# DS3_CONTROLLER_L.net
KiCad netlist of a schematic drawn in EasyEDA Pro
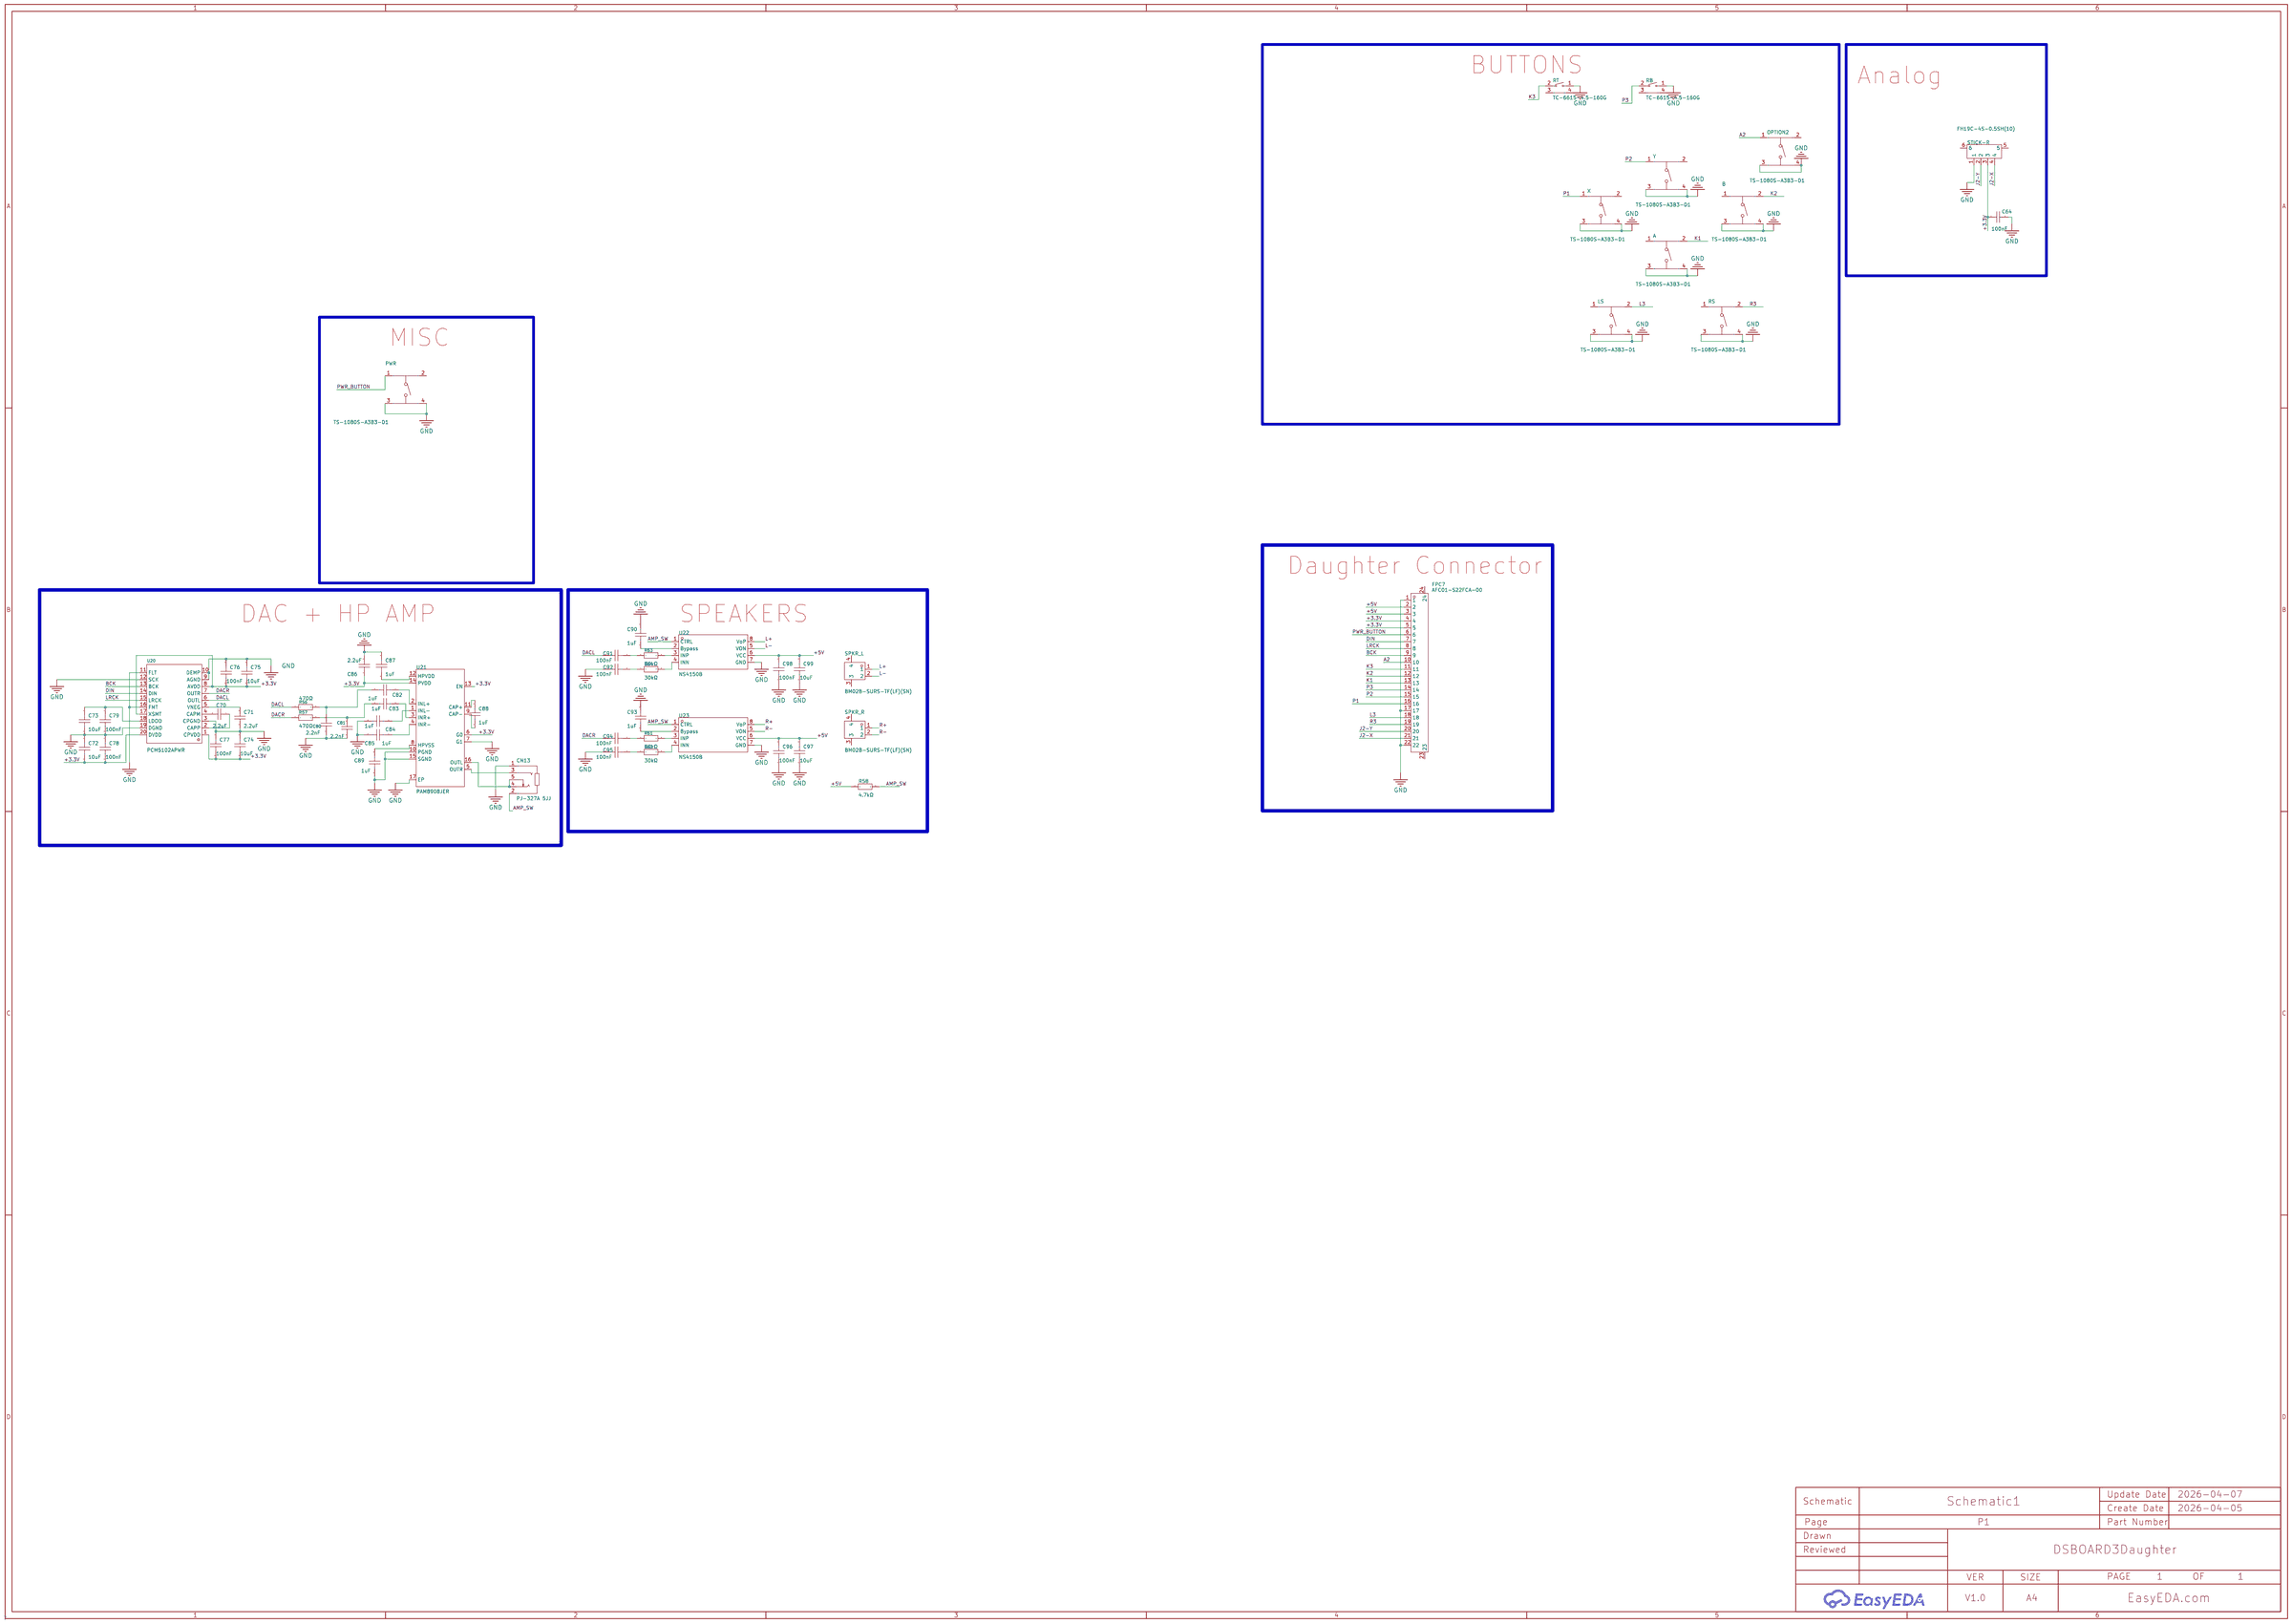
[diagram p0: schematic sheet]

(export (version "E")
  (design (tool "Eeschema 10.0.6"))
  (components
    (comp (ref "A")
      (value "TS-1080S-A3B3-D1")
      (footprint "easyedapro:KEY-SMD_4P-L6.0-W6.0-P4.50-LS9.5-BL")
      (fields (field (name "Manufacturer") "Yuandi(元迪)"))
      (libsource (lib "easyedapro") (part "K2-1102SP-C4SC-04"))
    )
    (comp (ref "B")
      (value "TS-1080S-A3B3-D1")
      (footprint "easyedapro:KEY-SMD_4P-L6.0-W6.0-P4.50-LS9.5-BL")
      (fields (field (name "Manufacturer") "Yuandi(元迪)"))
      (libsource (lib "easyedapro") (part "K2-1102SP-C4SC-04"))
    )
    (comp (ref "C64")
      (value "100nF")
      (footprint "easyedapro:C0402_NEW")
      (fields
        (field (name "Manufacturer Part") "CL05B104KO5NNNC")
        (field (name "Manufacturer") "SAMSUNG(三星)")
      )
      (libsource (lib "easyedapro") (part "100nF"))
    )
    (comp (ref "C70")
      (value "2.2uF")
      (footprint "easyedapro:C0603")
      (fields
        (field (name "Manufacturer Part") "CL10A225KO8NNNC")
        (field (name "Manufacturer") "SAMSUNG(三星)")
      )
      (libsource (lib "easyedapro") (part "CL10A225KO8NNNC"))
    )
    (comp (ref "C71")
      (value "2.2uF")
      (footprint "easyedapro:C0603")
      (fields
        (field (name "Manufacturer Part") "CL10A225KO8NNNC")
        (field (name "Manufacturer") "SAMSUNG(三星)")
      )
      (libsource (lib "easyedapro") (part "CL10A225KO8NNNC"))
    )
    (comp (ref "C72")
      (value "10uF")
      (footprint "easyedapro:C0805")
      (fields
        (field (name "Manufacturer Part") "GRM21BR61H106KE43L")
        (field (name "Manufacturer") "muRata(村田)")
      )
      (libsource (lib "easyedapro") (part "GRM21BR61H106KE43L"))
    )
    (comp (ref "C73")
      (value "10uF")
      (footprint "easyedapro:C0805")
      (fields
        (field (name "Manufacturer Part") "GRM21BR61H106KE43L")
        (field (name "Manufacturer") "muRata(村田)")
      )
      (libsource (lib "easyedapro") (part "GRM21BR61H106KE43L"))
    )
    (comp (ref "C74")
      (value "10uF")
      (footprint "easyedapro:C0805")
      (fields
        (field (name "Manufacturer Part") "GRM21BR61H106KE43L")
        (field (name "Manufacturer") "muRata(村田)")
      )
      (libsource (lib "easyedapro") (part "GRM21BR61H106KE43L"))
    )
    (comp (ref "C75")
      (value "10uF")
      (footprint "easyedapro:C0805")
      (fields
        (field (name "Manufacturer Part") "GRM21BR61H106KE43L")
        (field (name "Manufacturer") "muRata(村田)")
      )
      (libsource (lib "easyedapro") (part "GRM21BR61H106KE43L"))
    )
    (comp (ref "C76")
      (value "100nF")
      (footprint "easyedapro:C0603")
      (description "Capacitance:100nF Tolerance:±10% Tolerance:±10% Voltage Rating:50V Temperature Coefficient:X7R")
      (fields
        (field (name "Manufacturer Part") "CC0603KRX7R9BB104")
        (field (name "Manufacturer") "YAGEO(国巨)")
      )
      (libsource (lib "easyedapro") (part "CC0603KRX7R9BB104"))
    )
    (comp (ref "C77")
      (value "100nF")
      (footprint "easyedapro:C0603")
      (description "Capacitance:100nF Tolerance:±10% Tolerance:±10% Voltage Rating:50V Temperature Coefficient:X7R")
      (fields
        (field (name "Manufacturer Part") "CC0603KRX7R9BB104")
        (field (name "Manufacturer") "YAGEO(国巨)")
      )
      (libsource (lib "easyedapro") (part "CC0603KRX7R9BB104"))
    )
    (comp (ref "C78")
      (value "100nF")
      (footprint "easyedapro:C0603")
      (description "Capacitance:100nF Tolerance:±10% Tolerance:±10% Voltage Rating:50V Temperature Coefficient:X7R")
      (fields
        (field (name "Manufacturer Part") "CC0603KRX7R9BB104")
        (field (name "Manufacturer") "YAGEO(国巨)")
      )
      (libsource (lib "easyedapro") (part "CC0603KRX7R9BB104"))
    )
    (comp (ref "C79")
      (value "100nF")
      (footprint "easyedapro:C0603")
      (description "Capacitance:100nF Tolerance:±10% Tolerance:±10% Voltage Rating:50V Temperature Coefficient:X7R")
      (fields
        (field (name "Manufacturer Part") "CC0603KRX7R9BB104")
        (field (name "Manufacturer") "YAGEO(国巨)")
      )
      (libsource (lib "easyedapro") (part "CC0603KRX7R9BB104"))
    )
    (comp (ref "C80")
      (value "2.2nF")
      (footprint "easyedapro:C0805")
      (fields
        (field (name "Manufacturer Part") "CL21C222JBFNNNE")
        (field (name "Manufacturer") "SAMSUNG(三星)")
      )
      (libsource (lib "easyedapro") (part "CL21C222JBFNNNE"))
    )
    (comp (ref "C81")
      (value "2.2nF")
      (footprint "easyedapro:C0805")
      (fields
        (field (name "Manufacturer Part") "CL21C222JBFNNNE")
        (field (name "Manufacturer") "SAMSUNG(三星)")
      )
      (libsource (lib "easyedapro") (part "CL21C222JBFNNNE"))
    )
    (comp (ref "C82")
      (value "1uF")
      (footprint "easyedapro:C0603")
      (fields
        (field (name "Manufacturer Part") "CL10A105KB8NNNC")
        (field (name "Manufacturer") "SAMSUNG(三星)")
      )
      (libsource (lib "easyedapro") (part "CL10A105KB8NNNC"))
    )
    (comp (ref "C83")
      (value "1uF")
      (footprint "easyedapro:C0603")
      (fields
        (field (name "Manufacturer Part") "CL10A105KB8NNNC")
        (field (name "Manufacturer") "SAMSUNG(三星)")
      )
      (libsource (lib "easyedapro") (part "CL10A105KB8NNNC"))
    )
    (comp (ref "C84")
      (value "1uF")
      (footprint "easyedapro:C0603")
      (fields
        (field (name "Manufacturer Part") "CL10A105KB8NNNC")
        (field (name "Manufacturer") "SAMSUNG(三星)")
      )
      (libsource (lib "easyedapro") (part "CL10A105KB8NNNC"))
    )
    (comp (ref "C85")
      (value "1uF")
      (footprint "easyedapro:C0603")
      (fields
        (field (name "Manufacturer Part") "CL10A105KB8NNNC")
        (field (name "Manufacturer") "SAMSUNG(三星)")
      )
      (libsource (lib "easyedapro") (part "CL10A105KB8NNNC"))
    )
    (comp (ref "C86")
      (value "2.2uF")
      (footprint "easyedapro:C0603")
      (fields
        (field (name "Manufacturer Part") "CL10A225KO8NNNC")
        (field (name "Manufacturer") "SAMSUNG(三星)")
      )
      (libsource (lib "easyedapro") (part "CL10A225KO8NNNC"))
    )
    (comp (ref "C87")
      (value "1uF")
      (footprint "easyedapro:C0603")
      (fields
        (field (name "Manufacturer Part") "CL10A105KB8NNNC")
        (field (name "Manufacturer") "SAMSUNG(三星)")
      )
      (libsource (lib "easyedapro") (part "CL10A105KB8NNNC"))
    )
    (comp (ref "C88")
      (value "1uF")
      (footprint "easyedapro:C0603")
      (fields
        (field (name "Manufacturer Part") "CL10A105KB8NNNC")
        (field (name "Manufacturer") "SAMSUNG(三星)")
      )
      (libsource (lib "easyedapro") (part "CL10A105KB8NNNC"))
    )
    (comp (ref "C89")
      (value "1uF")
      (footprint "easyedapro:C0603")
      (fields
        (field (name "Manufacturer Part") "CL10A105KB8NNNC")
        (field (name "Manufacturer") "SAMSUNG(三星)")
      )
      (libsource (lib "easyedapro") (part "CL10A105KB8NNNC"))
    )
    (comp (ref "C90")
      (value "1uF")
      (footprint "easyedapro:C0603")
      (fields
        (field (name "Manufacturer Part") "CL10A105KB8NNNC")
        (field (name "Manufacturer") "SAMSUNG(三星)")
      )
      (libsource (lib "easyedapro") (part "CL10A105KB8NNNC"))
    )
    (comp (ref "C91")
      (value "100nF")
      (footprint "easyedapro:C0402")
      (fields
        (field (name "Manufacturer Part") "CL05B104KB54PNC")
        (field (name "Manufacturer") "SAMSUNG(三星)")
      )
      (libsource (lib "easyedapro") (part "CL05B104KB54PNC"))
    )
    (comp (ref "C92")
      (value "100nF")
      (footprint "easyedapro:C0402")
      (fields
        (field (name "Manufacturer Part") "CL05B104KB54PNC")
        (field (name "Manufacturer") "SAMSUNG(三星)")
      )
      (libsource (lib "easyedapro") (part "CL05B104KB54PNC"))
    )
    (comp (ref "C93")
      (value "1uF")
      (footprint "easyedapro:C0603")
      (fields
        (field (name "Manufacturer Part") "CL10A105KB8NNNC")
        (field (name "Manufacturer") "SAMSUNG(三星)")
      )
      (libsource (lib "easyedapro") (part "CL10A105KB8NNNC"))
    )
    (comp (ref "C94")
      (value "100nF")
      (footprint "easyedapro:C0402")
      (fields
        (field (name "Manufacturer Part") "CL05B104KB54PNC")
        (field (name "Manufacturer") "SAMSUNG(三星)")
      )
      (libsource (lib "easyedapro") (part "CL05B104KB54PNC"))
    )
    (comp (ref "C95")
      (value "100nF")
      (footprint "easyedapro:C0402")
      (fields
        (field (name "Manufacturer Part") "CL05B104KB54PNC")
        (field (name "Manufacturer") "SAMSUNG(三星)")
      )
      (libsource (lib "easyedapro") (part "CL05B104KB54PNC"))
    )
    (comp (ref "C96")
      (value "100nF")
      (footprint "easyedapro:C0402")
      (fields
        (field (name "Manufacturer Part") "CL05B104KB54PNC")
        (field (name "Manufacturer") "SAMSUNG(三星)")
      )
      (libsource (lib "easyedapro") (part "CL05B104KB54PNC"))
    )
    (comp (ref "C97")
      (value "10uF")
      (footprint "easyedapro:C0805")
      (fields
        (field (name "Manufacturer Part") "CL21A106KAYNNNE")
        (field (name "Manufacturer") "SAMSUNG(三星)")
      )
      (libsource (lib "easyedapro") (part "CL21A106KAYNNNE"))
    )
    (comp (ref "C98")
      (value "100nF")
      (footprint "easyedapro:C0402")
      (fields
        (field (name "Manufacturer Part") "CL05B104KB54PNC")
        (field (name "Manufacturer") "SAMSUNG(三星)")
      )
      (libsource (lib "easyedapro") (part "CL05B104KB54PNC"))
    )
    (comp (ref "C99")
      (value "10uF")
      (footprint "easyedapro:C0805")
      (fields
        (field (name "Manufacturer Part") "CL21A106KAYNNNE")
        (field (name "Manufacturer") "SAMSUNG(三星)")
      )
      (libsource (lib "easyedapro") (part "CL21A106KAYNNNE"))
    )
    (comp (ref "CN13")
      (value "PJ-327A 5JJ")
      (footprint "easyedapro:AUDIO-SMD_PJ-327A5JJ")
      (fields (field (name "Manufacturer") "SHOU HAN(首韩)"))
      (libsource (lib "easyedapro") (part "PJ-327A 5JJ"))
    )
    (comp (ref "FPC7")
      (value "AFC01-S22FCA-00")
      (footprint "easyedapro:FPC-SMD_P0.5-22P_FGS-XJ-H2.0")
      (fields (field (name "Manufacturer") "JS(钜硕电子)"))
      (libsource (lib "easyedapro") (part "fh12-22s-0.5sh(55)"))
    )
    (comp (ref "LS")
      (value "TS-1080S-A3B3-D1")
      (footprint "easyedapro:KEY-SMD_4P-L6.0-W6.0-P4.50-LS9.5-BL")
      (fields (field (name "Manufacturer") "Yuandi(元迪)"))
      (libsource (lib "easyedapro") (part "K2-1102SP-C4SC-04"))
    )
    (comp (ref "OPTION2")
      (value "TS-1080S-A3B3-D1")
      (footprint "easyedapro:KEY-SMD_4P-L6.0-W6.0-P4.50-LS9.5-BL")
      (fields (field (name "Manufacturer") "Yuandi(元迪)"))
      (libsource (lib "easyedapro") (part "K2-1102SP-C4SC-04"))
    )
    (comp (ref "PWR")
      (value "TS-1080S-A3B3-D1")
      (footprint "easyedapro:KEY-SMD_4P-L6.0-W6.0-P4.50-LS9.5-BL")
      (fields (field (name "Manufacturer") "Yuandi(元迪)"))
      (libsource (lib "easyedapro") (part "K2-1102SP-C4SC-04"))
    )
    (comp (ref "R56")
      (value "470Ω")
      (footprint "easyedapro:R0805")
      (fields
        (field (name "Manufacturer Part") "0805W8F4700T5E")
        (field (name "Manufacturer") "UNI-ROYAL(厚声)")
      )
      (libsource (lib "easyedapro") (part "0805W8F4700T5E"))
    )
    (comp (ref "R57")
      (value "470Ω")
      (footprint "easyedapro:R0805")
      (fields
        (field (name "Manufacturer Part") "0805W8F4700T5E")
        (field (name "Manufacturer") "UNI-ROYAL(厚声)")
      )
      (libsource (lib "easyedapro") (part "0805W8F4700T5E"))
    )
    (comp (ref "R58")
      (value "4.7kΩ")
      (footprint "easyedapro:R0603")
      (fields
        (field (name "Manufacturer Part") "0603WAF4701T5E")
        (field (name "Manufacturer") "UNI-ROYAL(厚声)")
      )
      (libsource (lib "easyedapro") (part "0603WAF4701T5E"))
    )
    (comp (ref "R61")
      (value "30kΩ")
      (footprint "easyedapro:R0603")
      (fields
        (field (name "Manufacturer Part") "0603WAF3002T5E")
        (field (name "Manufacturer") "UNI-ROYAL(厚声)")
      )
      (libsource (lib "easyedapro") (part "0603WAF3002T5E"))
    )
    (comp (ref "R62")
      (value "30kΩ")
      (footprint "easyedapro:R0603")
      (fields
        (field (name "Manufacturer Part") "0603WAF3002T5E")
        (field (name "Manufacturer") "UNI-ROYAL(厚声)")
      )
      (libsource (lib "easyedapro") (part "0603WAF3002T5E"))
    )
    (comp (ref "R63")
      (value "30kΩ")
      (footprint "easyedapro:R0603")
      (fields
        (field (name "Manufacturer Part") "0603WAF3002T5E")
        (field (name "Manufacturer") "UNI-ROYAL(厚声)")
      )
      (libsource (lib "easyedapro") (part "0603WAF3002T5E"))
    )
    (comp (ref "R64")
      (value "30kΩ")
      (footprint "easyedapro:R0603")
      (fields
        (field (name "Manufacturer Part") "0603WAF3002T5E")
        (field (name "Manufacturer") "UNI-ROYAL(厚声)")
      )
      (libsource (lib "easyedapro") (part "0603WAF3002T5E"))
    )
    (comp (ref "RB")
      (value "TC-6615-4.5-160G")
      (footprint "easyedapro:KEY-TH_TC-6615-4.5-160G")
      (fields (field (name "Manufacturer") "HCTL(华灿天禄)"))
      (libsource (lib "easyedapro") (part "TC-6615-4.5-160G"))
    )
    (comp (ref "RS")
      (value "TS-1080S-A3B3-D1")
      (footprint "easyedapro:KEY-SMD_4P-L6.0-W6.0-P4.50-LS9.5-BL")
      (fields (field (name "Manufacturer") "Yuandi(元迪)"))
      (libsource (lib "easyedapro") (part "K2-1102SP-C4SC-04"))
    )
    (comp (ref "RT")
      (value "TC-6615-4.5-160G")
      (footprint "easyedapro:KEY-TH_TC-6615-4.5-160G")
      (fields (field (name "Manufacturer") "HCTL(华灿天禄)"))
      (libsource (lib "easyedapro") (part "TC-6615-4.5-160G"))
    )
    (comp (ref "SPKR_L")
      (value "BM02B-SURS-TF(LF)(SN)")
      (footprint "easyedapro:CONN-SMD_2P-P0.80_BM02B-SURS-TF-LF-SN")
      (fields (field (name "Manufacturer") "JST"))
      (libsource (lib "easyedapro") (part "BM02B-SURS-TF(LF)(SN)"))
    )
    (comp (ref "SPKR_R")
      (value "BM02B-SURS-TF(LF)(SN)")
      (footprint "easyedapro:CONN-SMD_2P-P0.80_BM02B-SURS-TF-LF-SN")
      (fields (field (name "Manufacturer") "JST"))
      (libsource (lib "easyedapro") (part "BM02B-SURS-TF(LF)(SN)"))
    )
    (comp (ref "STICK-R")
      (value "FH19C-4S-0.5SH(10)")
      (fields (field (name "Manufacturer") "HRS(广濑)"))
      (libsource (lib "easyedapro") (part "fh34srj-4s-0.5sh(50)"))
    )
    (comp (ref "U20")
      (value "PCM5102APWR")
      (footprint "easyedapro:TSSOP-20_L6.5-W4.4-P0.65-LS6.4-BL")
      (fields (field (name "Manufacturer") "TI(德州仪器)"))
      (libsource (lib "easyedapro") (part "PCM5102APWR"))
    )
    (comp (ref "U21")
      (value "PAM8908JER")
      (footprint "easyedapro:QFN-16_L3.0-W3.0-P0.50-BL-EP1.7")
      (fields (field (name "Manufacturer") "DIODES(美台)"))
      (libsource (lib "easyedapro") (part "PAM8908JER"))
    )
    (comp (ref "U22")
      (value "NS4150B")
      (footprint "easyedapro:MSOP-8_L3.0-W3.0-P0.65-LS5.0-BL")
      (description "Class:Class D Output Power:3Wx1@4Ω Voltage - Supply:3V~5.25V Voltage - Supply:3V~5.25V")
      (fields (field (name "Manufacturer") "Nsiway(纳芯威)"))
      (libsource (lib "easyedapro") (part "NS4150"))
    )
    (comp (ref "U23")
      (value "NS4150B")
      (footprint "easyedapro:MSOP-8_L3.0-W3.0-P0.65-LS5.0-BL")
      (description "Class:Class D Output Power:3Wx1@4Ω Voltage - Supply:3V~5.25V Voltage - Supply:3V~5.25V")
      (fields (field (name "Manufacturer") "Nsiway(纳芯威)"))
      (libsource (lib "easyedapro") (part "NS4150"))
    )
    (comp (ref "X")
      (value "TS-1080S-A3B3-D1")
      (footprint "easyedapro:KEY-SMD_4P-L6.0-W6.0-P4.50-LS9.5-BL")
      (fields (field (name "Manufacturer") "Yuandi(元迪)"))
      (libsource (lib "easyedapro") (part "K2-1102SP-C4SC-04"))
    )
    (comp (ref "Y")
      (value "TS-1080S-A3B3-D1")
      (footprint "easyedapro:KEY-SMD_4P-L6.0-W6.0-P4.50-LS9.5-BL")
      (fields (field (name "Manufacturer") "Yuandi(元迪)"))
      (libsource (lib "easyedapro") (part "K2-1102SP-C4SC-04"))
    )
  )
  (nets
    (net (code "1") (name "/+3.3V") (class "Default")
      (node (ref "C64") (pin "1") (pinfunction "1_1") (pintype "input"))
      (node (ref "C72") (pin "2") (pinfunction "2_2") (pintype "unspecified"))
      (node (ref "C74") (pin "2") (pinfunction "2_2") (pintype "unspecified"))
      (node (ref "C75") (pin "2") (pinfunction "2_2") (pintype "unspecified"))
      (node (ref "C76") (pin "2") (pinfunction "2_2") (pintype "unspecified"))
      (node (ref "C77") (pin "2") (pinfunction "2_2") (pintype "unspecified"))
      (node (ref "C78") (pin "2") (pinfunction "2_2") (pintype "unspecified"))
      (node (ref "C86") (pin "1") (pinfunction "1_1") (pintype "input"))
      (node (ref "FPC7") (pin "4") (pinfunction "4_4") (pintype "input"))
      (node (ref "FPC7") (pin "5") (pinfunction "5_5") (pintype "input"))
      (node (ref "STICK-R") (pin "3") (pinfunction "3_3") (pintype "unspecified"))
      (node (ref "U20") (pin "1") (pinfunction "CPVDD_1") (pintype "input"))
      (node (ref "U20") (pin "17") (pinfunction "XSMT_17") (pintype "input"))
      (node (ref "U20") (pin "20") (pinfunction "DVDD_20") (pintype "input"))
      (node (ref "U20") (pin "8") (pinfunction "AVDD_8") (pintype "input"))
      (node (ref "U21") (pin "13") (pinfunction "EN_13") (pintype "unspecified"))
      (node (ref "U21") (pin "14") (pinfunction "PVDD_14") (pintype "unspecified"))
      (node (ref "U21") (pin "6") (pinfunction "G0_6") (pintype "unspecified"))
    )
    (net (code "2") (name "/+5V") (class "Default")
      (node (ref "C96") (pin "2") (pinfunction "2_2") (pintype "input"))
      (node (ref "C97") (pin "2") (pinfunction "2_2") (pintype "unspecified"))
      (node (ref "C98") (pin "2") (pinfunction "2_2") (pintype "input"))
      (node (ref "C99") (pin "2") (pinfunction "2_2") (pintype "unspecified"))
      (node (ref "FPC7") (pin "2") (pinfunction "2_2") (pintype "input"))
      (node (ref "FPC7") (pin "3") (pinfunction "3_3") (pintype "input"))
      (node (ref "R58") (pin "1") (pinfunction "1_1") (pintype "input"))
      (node (ref "U22") (pin "6") (pinfunction "VCC_6") (pintype "unspecified"))
      (node (ref "U23") (pin "6") (pinfunction "VCC_6") (pintype "unspecified"))
    )
    (net (code "3") (name "/A2") (class "Default")
      (node (ref "FPC7") (pin "10") (pinfunction "10_10") (pintype "input"))
      (node (ref "OPTION2") (pin "1") (pinfunction "1_1") (pintype "unspecified"))
    )
    (net (code "4") (name "/AMP_SW") (class "Default")
      (node (ref "CN13") (pin "2") (pinfunction "2_2") (pintype "unspecified"))
      (node (ref "R58") (pin "2") (pinfunction "2_2") (pintype "input"))
      (node (ref "U22") (pin "1") (pinfunction "CTRL_1") (pintype "unspecified"))
      (node (ref "U23") (pin "1") (pinfunction "CTRL_1") (pintype "unspecified"))
    )
    (net (code "5") (name "/BCK") (class "Default")
      (node (ref "FPC7") (pin "9") (pinfunction "9_9") (pintype "input"))
      (node (ref "U20") (pin "13") (pinfunction "BCK_13") (pintype "input"))
    )
    (net (code "6") (name "/DACL") (class "Default")
      (node (ref "C91") (pin "1") (pinfunction "1_1") (pintype "input"))
      (node (ref "R56") (pin "1") (pinfunction "1_1") (pintype "input"))
      (node (ref "U20") (pin "6") (pinfunction "OUTL_6") (pintype "input"))
    )
    (net (code "7") (name "/DACR") (class "Default")
      (node (ref "C94") (pin "1") (pinfunction "1_1") (pintype "input"))
      (node (ref "R57") (pin "1") (pinfunction "1_1") (pintype "input"))
      (node (ref "U20") (pin "7") (pinfunction "OUTR_7") (pintype "input"))
    )
    (net (code "8") (name "/DIN") (class "Default")
      (node (ref "FPC7") (pin "7") (pinfunction "7_7") (pintype "input"))
      (node (ref "U20") (pin "14") (pinfunction "DIN_14") (pintype "input"))
    )
    (net (code "9") (name "/J2-X") (class "Default")
      (node (ref "FPC7") (pin "21") (pinfunction "21_21") (pintype "input"))
      (node (ref "STICK-R") (pin "4") (pinfunction "4_4") (pintype "unspecified"))
    )
    (net (code "10") (name "/J2-Y") (class "Default")
      (node (ref "FPC7") (pin "20") (pinfunction "20_20") (pintype "input"))
      (node (ref "STICK-R") (pin "2") (pinfunction "2_2") (pintype "unspecified"))
    )
    (net (code "11") (name "/K1") (class "Default")
      (node (ref "A") (pin "2") (pinfunction "2_2") (pintype "unspecified"))
      (node (ref "FPC7") (pin "13") (pinfunction "13_13") (pintype "input"))
    )
    (net (code "12") (name "/K2") (class "Default")
      (node (ref "B") (pin "2") (pinfunction "2_2") (pintype "unspecified"))
      (node (ref "FPC7") (pin "12") (pinfunction "12_12") (pintype "input"))
    )
    (net (code "13") (name "/K3") (class "Default")
      (node (ref "FPC7") (pin "11") (pinfunction "11_11") (pintype "input"))
      (node (ref "RT") (pin "2") (pinfunction "2_2") (pintype "unspecified"))
    )
    (net (code "14") (name "/L+") (class "Default")
      (node (ref "SPKR_L") (pin "1") (pinfunction "1_1") (pintype "unspecified"))
      (node (ref "U22") (pin "8") (pinfunction "VoP_8") (pintype "unspecified"))
    )
    (net (code "15") (name "/L-") (class "Default")
      (node (ref "SPKR_L") (pin "2") (pinfunction "2_2") (pintype "unspecified"))
      (node (ref "U22") (pin "5") (pinfunction "VON_5") (pintype "unspecified"))
    )
    (net (code "16") (name "/L3") (class "Default")
      (node (ref "FPC7") (pin "18") (pinfunction "18_18") (pintype "input"))
      (node (ref "LS") (pin "2") (pinfunction "2_2") (pintype "unspecified"))
    )
    (net (code "17") (name "/LRCK") (class "Default")
      (node (ref "FPC7") (pin "8") (pinfunction "8_8") (pintype "input"))
      (node (ref "U20") (pin "15") (pinfunction "LRCK_15") (pintype "input"))
    )
    (net (code "18") (name "/P1") (class "Default")
      (node (ref "FPC7") (pin "16") (pinfunction "16_16") (pintype "input"))
      (node (ref "X") (pin "1") (pinfunction "1_1") (pintype "unspecified"))
    )
    (net (code "19") (name "/P2") (class "Default")
      (node (ref "FPC7") (pin "15") (pinfunction "15_15") (pintype "input"))
      (node (ref "Y") (pin "1") (pinfunction "1_1") (pintype "unspecified"))
    )
    (net (code "20") (name "/P3") (class "Default")
      (node (ref "FPC7") (pin "14") (pinfunction "14_14") (pintype "input"))
      (node (ref "RB") (pin "2") (pinfunction "2_2") (pintype "unspecified"))
    )
    (net (code "21") (name "/PWR_BUTTON") (class "Default")
      (node (ref "FPC7") (pin "6") (pinfunction "6_6") (pintype "input"))
      (node (ref "PWR") (pin "1") (pinfunction "1_1") (pintype "unspecified"))
    )
    (net (code "22") (name "/R+") (class "Default")
      (node (ref "SPKR_R") (pin "1") (pinfunction "1_1") (pintype "unspecified"))
      (node (ref "U23") (pin "8") (pinfunction "VoP_8") (pintype "unspecified"))
    )
    (net (code "23") (name "/R-") (class "Default")
      (node (ref "SPKR_R") (pin "2") (pinfunction "2_2") (pintype "unspecified"))
      (node (ref "U23") (pin "5") (pinfunction "VON_5") (pintype "unspecified"))
    )
    (net (code "24") (name "/R3") (class "Default")
      (node (ref "FPC7") (pin "19") (pinfunction "19_19") (pintype "input"))
      (node (ref "RS") (pin "2") (pinfunction "2_2") (pintype "unspecified"))
    )
    (net (code "25") (name "GND") (class "Default")
      (node (ref "A") (pin "3") (pinfunction "3_3") (pintype "unspecified"))
      (node (ref "A") (pin "4") (pinfunction "4_4") (pintype "unspecified"))
      (node (ref "B") (pin "3") (pinfunction "3_3") (pintype "unspecified"))
      (node (ref "B") (pin "4") (pinfunction "4_4") (pintype "unspecified"))
      (node (ref "C64") (pin "2") (pinfunction "2_2") (pintype "input"))
      (node (ref "C71") (pin "1") (pinfunction "1_1") (pintype "input"))
      (node (ref "C72") (pin "1") (pinfunction "1_1") (pintype "unspecified"))
      (node (ref "C73") (pin "2") (pinfunction "2_2") (pintype "unspecified"))
      (node (ref "C74") (pin "1") (pinfunction "1_1") (pintype "unspecified"))
      (node (ref "C75") (pin "1") (pinfunction "1_1") (pintype "unspecified"))
      (node (ref "C76") (pin "1") (pinfunction "1_1") (pintype "unspecified"))
      (node (ref "C77") (pin "1") (pinfunction "1_1") (pintype "unspecified"))
      (node (ref "C78") (pin "1") (pinfunction "1_1") (pintype "unspecified"))
      (node (ref "C79") (pin "2") (pinfunction "2_2") (pintype "unspecified"))
      (node (ref "C80") (pin "2") (pinfunction "2_2") (pintype "input"))
      (node (ref "C81") (pin "2") (pinfunction "2_2") (pintype "input"))
      (node (ref "C84") (pin "2") (pinfunction "2_2") (pintype "unspecified"))
      (node (ref "C85") (pin "2") (pinfunction "2_2") (pintype "unspecified"))
      (node (ref "C86") (pin "2") (pinfunction "2_2") (pintype "input"))
      (node (ref "C87") (pin "2") (pinfunction "2_2") (pintype "unspecified"))
      (node (ref "C89") (pin "1") (pinfunction "1_1") (pintype "unspecified"))
      (node (ref "C90") (pin "2") (pinfunction "2_2") (pintype "unspecified"))
      (node (ref "C92") (pin "1") (pinfunction "1_1") (pintype "input"))
      (node (ref "C93") (pin "2") (pinfunction "2_2") (pintype "unspecified"))
      (node (ref "C95") (pin "1") (pinfunction "1_1") (pintype "input"))
      (node (ref "C96") (pin "1") (pinfunction "1_1") (pintype "input"))
      (node (ref "C97") (pin "1") (pinfunction "1_1") (pintype "unspecified"))
      (node (ref "C98") (pin "1") (pinfunction "1_1") (pintype "input"))
      (node (ref "C99") (pin "1") (pinfunction "1_1") (pintype "unspecified"))
      (node (ref "CN13") (pin "1") (pinfunction "1_1") (pintype "unspecified"))
      (node (ref "FPC7") (pin "1") (pinfunction "1_1") (pintype "input"))
      (node (ref "FPC7") (pin "17") (pinfunction "17_17") (pintype "input"))
      (node (ref "FPC7") (pin "22") (pinfunction "22_22") (pintype "input"))
      (node (ref "LS") (pin "3") (pinfunction "3_3") (pintype "unspecified"))
      (node (ref "LS") (pin "4") (pinfunction "4_4") (pintype "unspecified"))
      (node (ref "OPTION2") (pin "3") (pinfunction "3_3") (pintype "unspecified"))
      (node (ref "OPTION2") (pin "4") (pinfunction "4_4") (pintype "unspecified"))
      (node (ref "PWR") (pin "3") (pinfunction "3_3") (pintype "unspecified"))
      (node (ref "PWR") (pin "4") (pinfunction "4_4") (pintype "unspecified"))
      (node (ref "RB") (pin "1") (pinfunction "1_1") (pintype "unspecified"))
      (node (ref "RS") (pin "3") (pinfunction "3_3") (pintype "unspecified"))
      (node (ref "RS") (pin "4") (pinfunction "4_4") (pintype "unspecified"))
      (node (ref "RT") (pin "1") (pinfunction "1_1") (pintype "unspecified"))
      (node (ref "STICK-R") (pin "1") (pinfunction "1_1") (pintype "unspecified"))
      (node (ref "U20") (pin "10") (pinfunction "DEMP_10") (pintype "input"))
      (node (ref "U20") (pin "11") (pinfunction "FLT_11") (pintype "input"))
      (node (ref "U20") (pin "12") (pinfunction "SCK_12") (pintype "input"))
      (node (ref "U20") (pin "16") (pinfunction "FMT_16") (pintype "input"))
      (node (ref "U20") (pin "19") (pinfunction "DGND_19") (pintype "input"))
      (node (ref "U20") (pin "3") (pinfunction "CPGND_3") (pintype "input"))
      (node (ref "U20") (pin "9") (pinfunction "AGND_9") (pintype "input"))
      (node (ref "U21") (pin "10") (pinfunction "PGND_10") (pintype "unspecified"))
      (node (ref "U21") (pin "15") (pinfunction "SGND_15") (pintype "unspecified"))
      (node (ref "U21") (pin "17") (pinfunction "EP_17") (pintype "unspecified"))
      (node (ref "U21") (pin "7") (pinfunction "G1_7") (pintype "unspecified"))
      (node (ref "U22") (pin "7") (pinfunction "GND_7") (pintype "unspecified"))
      (node (ref "U23") (pin "7") (pinfunction "GND_7") (pintype "unspecified"))
      (node (ref "X") (pin "3") (pinfunction "3_3") (pintype "unspecified"))
      (node (ref "X") (pin "4") (pinfunction "4_4") (pintype "unspecified"))
      (node (ref "Y") (pin "3") (pinfunction "3_3") (pintype "unspecified"))
      (node (ref "Y") (pin "4") (pinfunction "4_4") (pintype "unspecified"))
    )
    (net (code "26") (name "Net-(C80-Pad1)") (class "Default")
      (node (ref "C80") (pin "1") (pinfunction "1_1") (pintype "input"))
      (node (ref "C82") (pin "2") (pinfunction "2_2") (pintype "unspecified"))
      (node (ref "R56") (pin "2") (pinfunction "2_2") (pintype "input"))
    )
    (net (code "27") (name "Net-(C81-Pad1)") (class "Default")
      (node (ref "C81") (pin "1") (pinfunction "1_1") (pintype "input"))
      (node (ref "C83") (pin "2") (pinfunction "2_2") (pintype "unspecified"))
      (node (ref "R57") (pin "2") (pinfunction "2_2") (pintype "input"))
    )
    (net (code "28") (name "Net-(C91-Pad2)") (class "Default")
      (node (ref "C91") (pin "2") (pinfunction "2_2") (pintype "input"))
      (node (ref "R63") (pin "1") (pinfunction "1_1") (pintype "input"))
    )
    (net (code "29") (name "Net-(C92-Pad2)") (class "Default")
      (node (ref "C92") (pin "2") (pinfunction "2_2") (pintype "input"))
      (node (ref "R64") (pin "1") (pinfunction "1_1") (pintype "input"))
    )
    (net (code "30") (name "Net-(C94-Pad2)") (class "Default")
      (node (ref "C94") (pin "2") (pinfunction "2_2") (pintype "input"))
      (node (ref "R61") (pin "1") (pinfunction "1_1") (pintype "input"))
    )
    (net (code "31") (name "Net-(C95-Pad2)") (class "Default")
      (node (ref "C95") (pin "2") (pinfunction "2_2") (pintype "input"))
      (node (ref "R62") (pin "1") (pinfunction "1_1") (pintype "input"))
    )
    (net (code "32") (name "Net-(U20-CAPM)") (class "Default")
      (node (ref "C70") (pin "2") (pinfunction "2_2") (pintype "input"))
      (node (ref "U20") (pin "4") (pinfunction "CAPM_4") (pintype "input"))
    )
    (net (code "33") (name "Net-(U20-CAPP)") (class "Default")
      (node (ref "C70") (pin "1") (pinfunction "1_1") (pintype "input"))
      (node (ref "U20") (pin "2") (pinfunction "CAPP_2") (pintype "input"))
    )
    (net (code "34") (name "Net-(U20-LDOO)") (class "Default")
      (node (ref "C73") (pin "1") (pinfunction "1_1") (pintype "unspecified"))
      (node (ref "C79") (pin "1") (pinfunction "1_1") (pintype "unspecified"))
      (node (ref "U20") (pin "18") (pinfunction "LDOO_18") (pintype "input"))
    )
    (net (code "35") (name "Net-(U20-VNEG)") (class "Default")
      (node (ref "C71") (pin "2") (pinfunction "2_2") (pintype "input"))
      (node (ref "U20") (pin "5") (pinfunction "VNEG_5") (pintype "input"))
    )
    (net (code "36") (name "Net-(U21-CAP+)") (class "Default")
      (node (ref "C88") (pin "2") (pinfunction "2_2") (pintype "unspecified"))
      (node (ref "U21") (pin "11") (pinfunction "CAP+_11") (pintype "unspecified"))
    )
    (net (code "37") (name "Net-(U21-CAP-)") (class "Default")
      (node (ref "C88") (pin "1") (pinfunction "1_1") (pintype "unspecified"))
      (node (ref "U21") (pin "9") (pinfunction "CAP-_9") (pintype "unspecified"))
    )
    (net (code "38") (name "Net-(U21-HPVDD)") (class "Default")
      (node (ref "C87") (pin "1") (pinfunction "1_1") (pintype "unspecified"))
      (node (ref "U21") (pin "12") (pinfunction "HPVDD_12") (pintype "unspecified"))
    )
    (net (code "39") (name "Net-(U21-HPVSS)") (class "Default")
      (node (ref "C89") (pin "2") (pinfunction "2_2") (pintype "unspecified"))
      (node (ref "U21") (pin "8") (pinfunction "HPVSS_8") (pintype "unspecified"))
    )
    (net (code "40") (name "Net-(U21-INL+)") (class "Default")
      (node (ref "C82") (pin "1") (pinfunction "1_1") (pintype "unspecified"))
      (node (ref "U21") (pin "2") (pinfunction "INL+_2") (pintype "unspecified"))
    )
    (net (code "41") (name "Net-(U21-INL-)") (class "Default")
      (node (ref "C84") (pin "1") (pinfunction "1_1") (pintype "unspecified"))
      (node (ref "U21") (pin "1") (pinfunction "INL-_1") (pintype "unspecified"))
    )
    (net (code "42") (name "Net-(U21-INR+)") (class "Default")
      (node (ref "C83") (pin "1") (pinfunction "1_1") (pintype "unspecified"))
      (node (ref "U21") (pin "3") (pinfunction "INR+_3") (pintype "unspecified"))
    )
    (net (code "43") (name "Net-(U21-INR-)") (class "Default")
      (node (ref "C85") (pin "1") (pinfunction "1_1") (pintype "unspecified"))
      (node (ref "U21") (pin "4") (pinfunction "INR-_4") (pintype "unspecified"))
    )
    (net (code "44") (name "Net-(U21-OUTL)") (class "Default")
      (node (ref "CN13") (pin "4") (pinfunction "4_4") (pintype "unspecified"))
      (node (ref "CN13") (pin "5") (pinfunction "5_5") (pintype "unspecified"))
      (node (ref "U21") (pin "16") (pinfunction "OUTL_16") (pintype "unspecified"))
    )
    (net (code "45") (name "Net-(U21-OUTR)") (class "Default")
      (node (ref "CN13") (pin "3") (pinfunction "3_3") (pintype "unspecified"))
      (node (ref "U21") (pin "5") (pinfunction "OUTR_5") (pintype "unspecified"))
    )
    (net (code "46") (name "Net-(U22-Bypass)") (class "Default")
      (node (ref "C90") (pin "1") (pinfunction "1_1") (pintype "unspecified"))
      (node (ref "U22") (pin "2") (pinfunction "Bypass_2") (pintype "unspecified"))
    )
    (net (code "47") (name "Net-(U22-INN)") (class "Default")
      (node (ref "R64") (pin "2") (pinfunction "2_2") (pintype "input"))
      (node (ref "U22") (pin "4") (pinfunction "INN_4") (pintype "unspecified"))
    )
    (net (code "48") (name "Net-(U22-INP)") (class "Default")
      (node (ref "R63") (pin "2") (pinfunction "2_2") (pintype "input"))
      (node (ref "U22") (pin "3") (pinfunction "INP_3") (pintype "unspecified"))
    )
    (net (code "49") (name "Net-(U23-Bypass)") (class "Default")
      (node (ref "C93") (pin "1") (pinfunction "1_1") (pintype "unspecified"))
      (node (ref "U23") (pin "2") (pinfunction "Bypass_2") (pintype "unspecified"))
    )
    (net (code "50") (name "Net-(U23-INN)") (class "Default")
      (node (ref "R62") (pin "2") (pinfunction "2_2") (pintype "input"))
      (node (ref "U23") (pin "4") (pinfunction "INN_4") (pintype "unspecified"))
    )
    (net (code "51") (name "Net-(U23-INP)") (class "Default")
      (node (ref "R61") (pin "2") (pinfunction "2_2") (pintype "input"))
      (node (ref "U23") (pin "3") (pinfunction "INP_3") (pintype "unspecified"))
    )
    (net (code "52") (name "unconnected-(A-Pad1)") (class "Default")
      (node (ref "A") (pin "1") (pinfunction "1_1") (pintype "unspecified"))
    )
    (net (code "53") (name "unconnected-(B-Pad1)") (class "Default")
      (node (ref "B") (pin "1") (pinfunction "1_1") (pintype "unspecified"))
    )
    (net (code "54") (name "unconnected-(FPC7-Pad23)") (class "Default")
      (node (ref "FPC7") (pin "23") (pinfunction "23_23") (pintype "input"))
    )
    (net (code "55") (name "unconnected-(FPC7-Pad24)") (class "Default")
      (node (ref "FPC7") (pin "24") (pinfunction "24_24") (pintype "input"))
    )
    (net (code "56") (name "unconnected-(LS-Pad1)") (class "Default")
      (node (ref "LS") (pin "1") (pinfunction "1_1") (pintype "unspecified"))
    )
    (net (code "57") (name "unconnected-(OPTION2-Pad2)") (class "Default")
      (node (ref "OPTION2") (pin "2") (pinfunction "2_2") (pintype "unspecified"))
    )
    (net (code "58") (name "unconnected-(PWR-Pad2)") (class "Default")
      (node (ref "PWR") (pin "2") (pinfunction "2_2") (pintype "unspecified"))
    )
    (net (code "59") (name "unconnected-(RB-Pad3)") (class "Default")
      (node (ref "RB") (pin "3") (pinfunction "3_3") (pintype "unspecified"))
    )
    (net (code "60") (name "unconnected-(RB-Pad4)") (class "Default")
      (node (ref "RB") (pin "4") (pinfunction "4_4") (pintype "unspecified"))
    )
    (net (code "61") (name "unconnected-(RS-Pad1)") (class "Default")
      (node (ref "RS") (pin "1") (pinfunction "1_1") (pintype "unspecified"))
    )
    (net (code "62") (name "unconnected-(RT-Pad3)") (class "Default")
      (node (ref "RT") (pin "3") (pinfunction "3_3") (pintype "unspecified"))
    )
    (net (code "63") (name "unconnected-(RT-Pad4)") (class "Default")
      (node (ref "RT") (pin "4") (pinfunction "4_4") (pintype "unspecified"))
    )
    (net (code "64") (name "unconnected-(SPKR_L-Pad3)") (class "Default")
      (node (ref "SPKR_L") (pin "3") (pinfunction "3_3") (pintype "unspecified"))
    )
    (net (code "65") (name "unconnected-(SPKR_L-Pad4)") (class "Default")
      (node (ref "SPKR_L") (pin "4") (pinfunction "4_4") (pintype "unspecified"))
    )
    (net (code "66") (name "unconnected-(SPKR_R-Pad3)") (class "Default")
      (node (ref "SPKR_R") (pin "3") (pinfunction "3_3") (pintype "unspecified"))
    )
    (net (code "67") (name "unconnected-(SPKR_R-Pad4)") (class "Default")
      (node (ref "SPKR_R") (pin "4") (pinfunction "4_4") (pintype "unspecified"))
    )
    (net (code "68") (name "unconnected-(STICK-R-Pad5)") (class "Default")
      (node (ref "STICK-R") (pin "5") (pinfunction "5_5") (pintype "unspecified"))
    )
    (net (code "69") (name "unconnected-(STICK-R-Pad6)") (class "Default")
      (node (ref "STICK-R") (pin "6") (pinfunction "6_6") (pintype "unspecified"))
    )
    (net (code "70") (name "unconnected-(X-Pad2)") (class "Default")
      (node (ref "X") (pin "2") (pinfunction "2_2") (pintype "unspecified"))
    )
    (net (code "71") (name "unconnected-(Y-Pad2)") (class "Default")
      (node (ref "Y") (pin "2") (pinfunction "2_2") (pintype "unspecified"))
    )
  )
)
